# ProPrj_Amy_From_SF.net
KiCad netlist of a schematic drawn in EasyEDA Pro
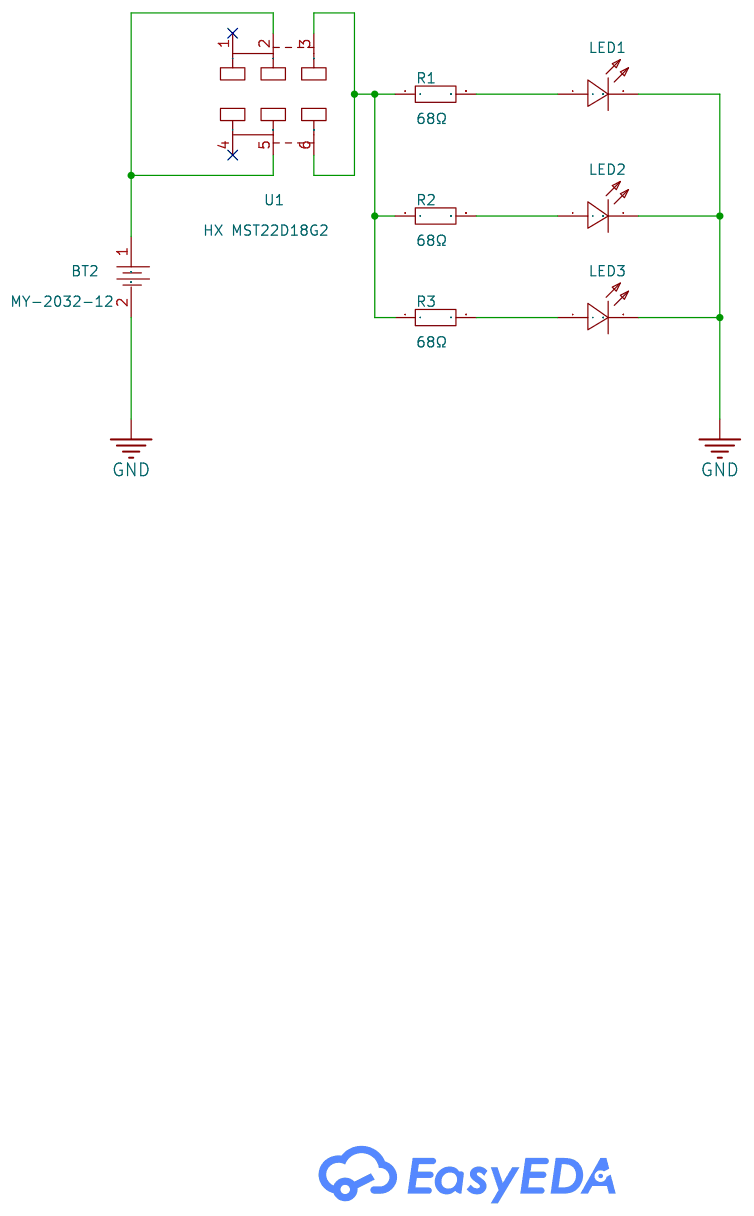
[diagram p0: schematic sheet]

(export (version "E")
  (design (tool "Eeschema 10.0.6"))
  (components
    (comp (ref "BT2")
      (value "MY-2032-12")
      (footprint "easyedapro:BAT-SMD_MY-2032-12")
      (fields (field (name "Manufacturer") "MYOUNG(美阳)"))
      (libsource (lib "easyedapro") (part "MY-2032-12"))
    )
    (comp (ref "LED1")
      (value "TJ-L5FYTGCRTFCSFLC2R-A5")
      (footprint "easyedapro:LED-TH_BD5.8-P2.54-FD")
      (fields (field (name "Manufacturer") "TOGIALED(统佳)"))
      (libsource (lib "easyedapro") (part "TJ-L5FYTGCRTFCSFLC2R-A5"))
    )
    (comp (ref "LED2")
      (value "TJ-L5FYTGCRTFCSFLC2R-A5")
      (footprint "easyedapro:LED-TH_BD5.8-P2.54-FD")
      (fields (field (name "Manufacturer") "TOGIALED(统佳)"))
      (libsource (lib "easyedapro") (part "TJ-L5FYTGCRTFCSFLC2R-A5"))
    )
    (comp (ref "LED3")
      (value "TJ-L5FYTGCRTFCSFLC2R-A5")
      (footprint "easyedapro:LED-TH_BD5.8-P2.54-FD")
      (fields (field (name "Manufacturer") "TOGIALED(统佳)"))
      (libsource (lib "easyedapro") (part "TJ-L5FYTGCRTFCSFLC2R-A5"))
    )
    (comp (ref "R1")
      (value "68Ω")
      (footprint "easyedapro:R0805")
      (fields
        (field (name "Manufacturer Part") "0805W8F680JT5E")
        (field (name "Manufacturer") "UNI-ROYAL(厚声)")
      )
      (libsource (lib "easyedapro") (part "0805W8F680JT5E"))
    )
    (comp (ref "R2")
      (value "68Ω")
      (footprint "easyedapro:R0805")
      (fields
        (field (name "Manufacturer Part") "0805W8F680JT5E")
        (field (name "Manufacturer") "UNI-ROYAL(厚声)")
      )
      (libsource (lib "easyedapro") (part "0805W8F680JT5E"))
    )
    (comp (ref "R3")
      (value "68Ω")
      (footprint "easyedapro:R0805")
      (fields
        (field (name "Manufacturer Part") "0805W8F680JT5E")
        (field (name "Manufacturer") "UNI-ROYAL(厚声)")
      )
      (libsource (lib "easyedapro") (part "0805W8F680JT5E"))
    )
    (comp (ref "U1")
      (value "HX MST22D18G2")
      (footprint "easyedapro:SW-SMD_MST22D18G2")
      (fields (field (name "Manufacturer") "hanxia(韩下)"))
      (libsource (lib "easyedapro") (part "HX MST22D18G2"))
    )
  )
  (nets
    (net (code "1") (name "GND") (class "Default")
      (node (ref "BT2") (pin "2") (pinfunction "2_2") (pintype "input"))
      (node (ref "LED1") (pin "2") (pinfunction "C_2") (pintype "unspecified"))
      (node (ref "LED2") (pin "2") (pinfunction "C_2") (pintype "unspecified"))
      (node (ref "LED3") (pin "2") (pinfunction "C_2") (pintype "unspecified"))
    )
    (net (code "2") (name "Net-(BT2-Pad1)") (class "Default")
      (node (ref "BT2") (pin "1") (pinfunction "1_1") (pintype "input"))
      (node (ref "U1") (pin "2") (pinfunction "2_2") (pintype "unspecified"))
      (node (ref "U1") (pin "5") (pinfunction "5_5") (pintype "unspecified"))
    )
    (net (code "3") (name "Net-(LED1-A)") (class "Default")
      (node (ref "LED1") (pin "1") (pinfunction "A_1") (pintype "unspecified"))
      (node (ref "R1") (pin "2") (pinfunction "2_2") (pintype "input"))
    )
    (net (code "4") (name "Net-(LED2-A)") (class "Default")
      (node (ref "LED2") (pin "1") (pinfunction "A_1") (pintype "unspecified"))
      (node (ref "R2") (pin "2") (pinfunction "2_2") (pintype "input"))
    )
    (net (code "5") (name "Net-(LED3-A)") (class "Default")
      (node (ref "LED3") (pin "1") (pinfunction "A_1") (pintype "unspecified"))
      (node (ref "R3") (pin "2") (pinfunction "2_2") (pintype "input"))
    )
    (net (code "6") (name "Net-(R1-Pad1)") (class "Default")
      (node (ref "R1") (pin "1") (pinfunction "1_1") (pintype "input"))
      (node (ref "R2") (pin "1") (pinfunction "1_1") (pintype "input"))
      (node (ref "R3") (pin "1") (pinfunction "1_1") (pintype "input"))
      (node (ref "U1") (pin "3") (pinfunction "3_3") (pintype "unspecified"))
      (node (ref "U1") (pin "6") (pinfunction "6_6") (pintype "unspecified"))
    )
    (net (code "7") (name "unconnected-(U1-Pad1)") (class "Default")
      (node (ref "U1") (pin "1") (pinfunction "1_1") (pintype "unspecified+no_connect"))
    )
    (net (code "8") (name "unconnected-(U1-Pad4)") (class "Default")
      (node (ref "U1") (pin "4") (pinfunction "4_4") (pintype "unspecified+no_connect"))
    )
  )
)
